# BT.net
KiCad netlist of a schematic drawn in Altium Designer
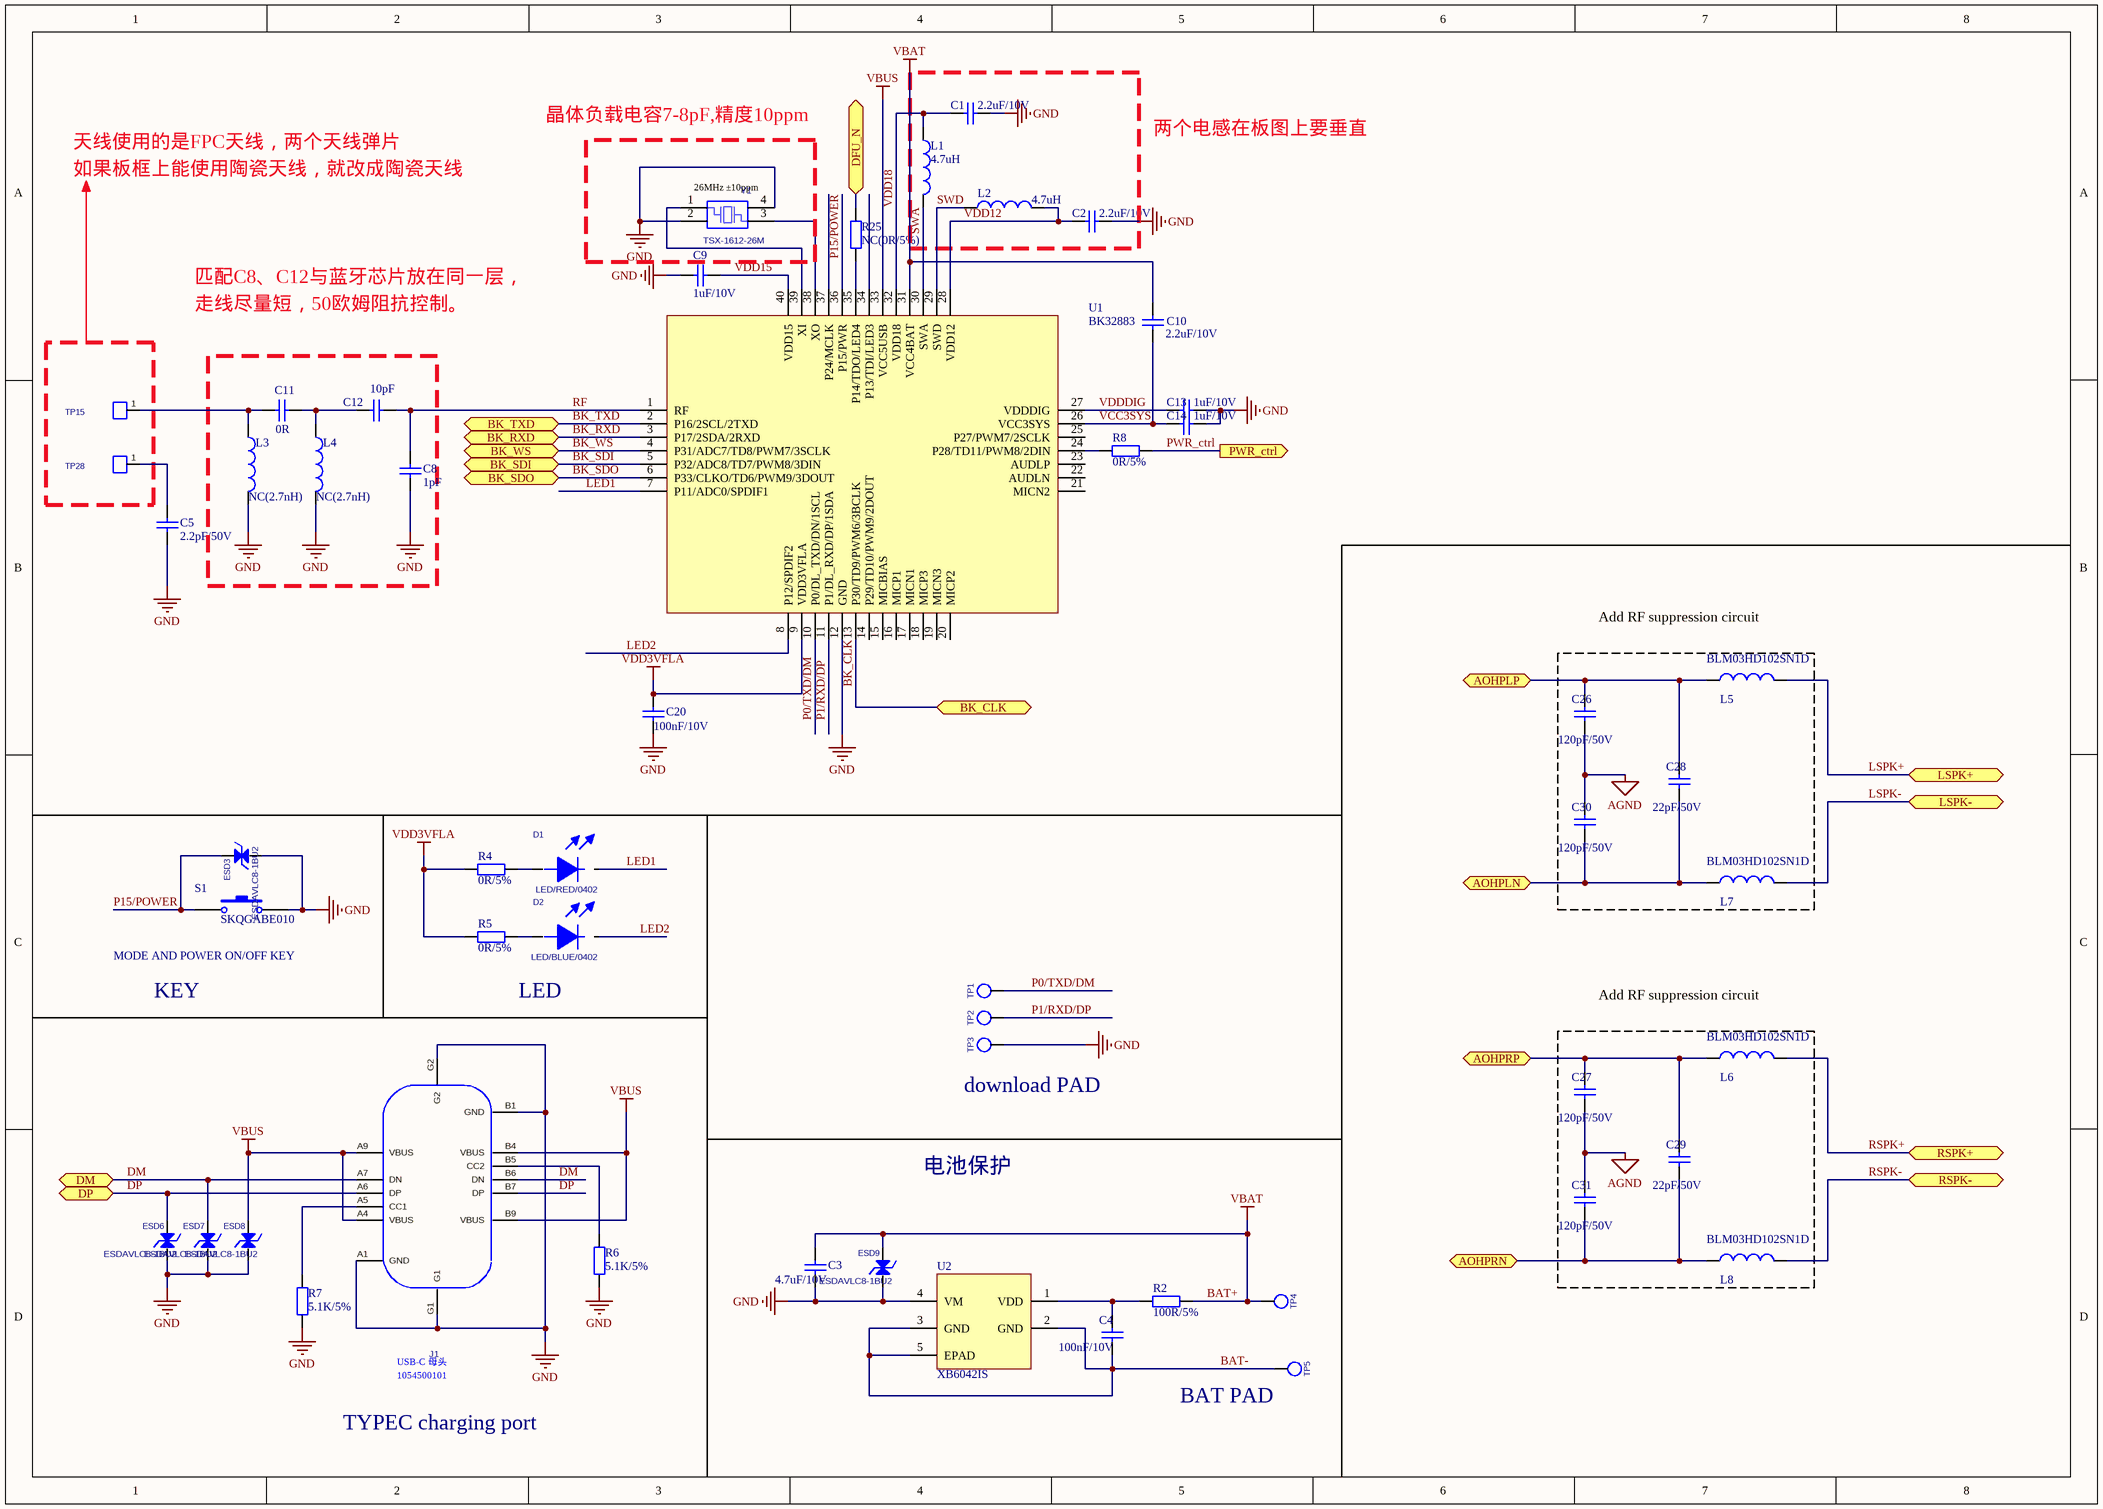
[diagram p0: BT .SchDoc]

(export (version "E")
  (design (tool "Eeschema 10.0.6"))
  (components
    (comp (ref "C1")
      (value "2.2uF/10V")
      (footprint "C0402")
      (description "Capacitor (Semiconductor SIM Model)")
      (fields (field (name "PUBLISHER") "Altium Limited"))
      (libsource (lib "Miscellaneous Devices") (part "Cap Semi"))
    )
    (comp (ref "C2")
      (value "2.2uF/10V")
      (footprint "C0402")
      (description "Capacitor (Semiconductor SIM Model)")
      (fields (field (name "PUBLISHER") "Altium Limited"))
      (libsource (lib "Miscellaneous Devices") (part "Cap Semi"))
    )
    (comp (ref "C3")
      (value "4.7uF/10V")
      (footprint "C0402")
      (description "Capacitor (Semiconductor SIM Model)")
      (fields (field (name "PUBLISHER") "Altium Limited"))
      (libsource (lib "Miscellaneous Devices") (part "Cap Semi"))
    )
    (comp (ref "C4")
      (value "100nF/10V")
      (footprint "0201")
      (description "Capacitor (Semiconductor SIM Model)")
      (fields (field (name "PUBLISHER") "Altium Limited"))
      (libsource (lib "Miscellaneous Devices") (part "Cap Semi"))
    )
    (comp (ref "C5")
      (value "2.2pF/50V")
      (footprint "0201")
      (description "Capacitor (Semiconductor SIM Model)")
      (fields (field (name "PUBLISHER") "Altium Limited"))
      (libsource (lib "Miscellaneous Devices") (part "Cap Semi"))
    )
    (comp (ref "C8")
      (value "1pF")
      (footprint "0201")
      (description "Capacitor (Semiconductor SIM Model)")
      (fields (field (name "PUBLISHER") "Altium Limited"))
      (libsource (lib "Miscellaneous Devices") (part "Cap Semi"))
    )
    (comp (ref "C9")
      (value "1uF/10V")
      (footprint "0201")
      (description "Capacitor (Semiconductor SIM Model)")
      (fields (field (name "PUBLISHER") "Altium Limited"))
      (libsource (lib "Miscellaneous Devices") (part "Cap Semi"))
    )
    (comp (ref "C10")
      (value "2.2uF/10V")
      (footprint "C0402")
      (description "Capacitor (Semiconductor SIM Model)")
      (fields (field (name "PUBLISHER") "Altium Limited"))
      (libsource (lib "Miscellaneous Devices") (part "Cap Semi"))
    )
    (comp (ref "C11")
      (value "0R")
      (footprint "0201")
      (description "Capacitor (Semiconductor SIM Model)")
      (fields (field (name "PUBLISHER") "Altium Limited"))
      (libsource (lib "Miscellaneous Devices") (part "Cap Semi"))
    )
    (comp (ref "C12")
      (value "10pF")
      (footprint "0201")
      (description "Capacitor (Semiconductor SIM Model)")
      (fields (field (name "PUBLISHER") "Altium Limited"))
      (libsource (lib "Miscellaneous Devices") (part "Cap Semi"))
    )
    (comp (ref "C13")
      (value "1uF/10V")
      (footprint "0201")
      (description "Capacitor (Semiconductor SIM Model)")
      (fields (field (name "PUBLISHER") "Altium Limited"))
      (libsource (lib "Miscellaneous Devices") (part "Cap Semi"))
    )
    (comp (ref "C14")
      (value "1uF/10V")
      (footprint "0201")
      (description "Capacitor (Semiconductor SIM Model)")
      (fields (field (name "PUBLISHER") "Altium Limited"))
      (libsource (lib "Miscellaneous Devices") (part "Cap Semi"))
    )
    (comp (ref "C20")
      (value "100nF/10V")
      (footprint "0201")
      (description "Capacitor (Semiconductor SIM Model)")
      (fields (field (name "PUBLISHER") "Altium Limited"))
      (libsource (lib "Miscellaneous Devices") (part "Cap Semi"))
    )
    (comp (ref "C26")
      (value "120pF/50V")
      (footprint "0201")
      (description "Capacitor (Semiconductor SIM Model)")
      (fields (field (name "PUBLISHER") "Altium Limited"))
      (libsource (lib "Miscellaneous Devices") (part "Cap Semi"))
    )
    (comp (ref "C27")
      (value "120pF/50V")
      (footprint "0201")
      (description "Capacitor (Semiconductor SIM Model)")
      (fields (field (name "PUBLISHER") "Altium Limited"))
      (libsource (lib "Miscellaneous Devices") (part "Cap Semi"))
    )
    (comp (ref "C28")
      (value "22pF/50V")
      (footprint "0201")
      (description "Capacitor (Semiconductor SIM Model)")
      (fields (field (name "PUBLISHER") "Altium Limited"))
      (libsource (lib "Miscellaneous Devices") (part "Cap Semi"))
    )
    (comp (ref "C29")
      (value "22pF/50V")
      (footprint "0201")
      (description "Capacitor (Semiconductor SIM Model)")
      (fields (field (name "PUBLISHER") "Altium Limited"))
      (libsource (lib "Miscellaneous Devices") (part "Cap Semi"))
    )
    (comp (ref "C30")
      (value "120pF/50V")
      (footprint "0201")
      (description "Capacitor (Semiconductor SIM Model)")
      (fields (field (name "PUBLISHER") "Altium Limited"))
      (libsource (lib "Miscellaneous Devices") (part "Cap Semi"))
    )
    (comp (ref "C31")
      (value "120pF/50V")
      (footprint "0201")
      (description "Capacitor (Semiconductor SIM Model)")
      (fields (field (name "PUBLISHER") "Altium Limited"))
      (libsource (lib "Miscellaneous Devices") (part "Cap Semi"))
    )
    (comp (ref "D1")
      (value "LED/RED/0402")
      (footprint "LED0402")
      (libsource (lib "EVB-SCH-LCD-202003152") (part "LED0603"))
    )
    (comp (ref "D2")
      (value "LED/BLUE/0402")
      (footprint "LED0402")
      (libsource (lib "EVB-SCH-LCD-202003152") (part "LED0603"))
    )
    (comp (ref "ESD3")
      (value "ESDAVLC8-1BU2")
      (footprint "0201")
      (libsource (lib "EVB-SCH-LCD-202003152") (part "ESD"))
    )
    (comp (ref "ESD6")
      (value "ESDAVLC8-1BU2")
      (footprint "0201")
      (libsource (lib "EVB-SCH-LCD-202003152") (part "ESD"))
    )
    (comp (ref "ESD7")
      (value "ESDAVLC8-1BU2")
      (footprint "0201")
      (libsource (lib "EVB-SCH-LCD-202003152") (part "ESD"))
    )
    (comp (ref "ESD8")
      (value "ESDAVLC8-1BU2")
      (footprint "0201")
      (libsource (lib "EVB-SCH-LCD-202003152") (part "ESD"))
    )
    (comp (ref "ESD9")
      (value "ESDAVLC8-1BU2")
      (footprint "0201")
      (libsource (lib "EVB-SCH-LCD-202003152") (part "ESD"))
    )
    (comp (ref "J1")
      (value "TYPEC")
      (footprint "USB-TYPEC - 12")
      (libsource (lib "EVB-SCH-LCD-202003152") (part "TYPEC"))
    )
    (comp (ref "L1")
      (value "4.7uH")
      (footprint "R0603")
      (description "Inductor")
      (fields (field (name "PUBLISHER") "Altium Limited"))
      (libsource (lib "Miscellaneous Devices") (part "Inductor"))
    )
    (comp (ref "L2")
      (value "4.7uH")
      (footprint "R0603")
      (description "Inductor")
      (fields (field (name "PUBLISHER") "Altium Limited"))
      (libsource (lib "Miscellaneous Devices") (part "Inductor"))
    )
    (comp (ref "L3")
      (value "NC(2.7nH)")
      (footprint "0201")
      (description "Inductor")
      (fields (field (name "PUBLISHER") "Altium Limited"))
      (libsource (lib "Miscellaneous Devices") (part "Inductor"))
    )
    (comp (ref "L4")
      (value "NC(2.7nH)")
      (footprint "0201")
      (description "Inductor")
      (fields (field (name "PUBLISHER") "Altium Limited"))
      (libsource (lib "Miscellaneous Devices") (part "Inductor"))
    )
    (comp (ref "L5")
      (value "BLM03HD102SN1D")
      (footprint "0201")
      (description "Inductor")
      (fields (field (name "PUBLISHER") "Altium Limited"))
      (libsource (lib "Miscellaneous Devices") (part "Inductor"))
    )
    (comp (ref "L6")
      (value "BLM03HD102SN1D")
      (footprint "0201")
      (description "Inductor")
      (fields (field (name "PUBLISHER") "Altium Limited"))
      (libsource (lib "Miscellaneous Devices") (part "Inductor"))
    )
    (comp (ref "L7")
      (value "BLM03HD102SN1D")
      (footprint "0201")
      (description "Inductor")
      (fields (field (name "PUBLISHER") "Altium Limited"))
      (libsource (lib "Miscellaneous Devices") (part "Inductor"))
    )
    (comp (ref "L8")
      (value "BLM03HD102SN1D")
      (footprint "0201")
      (description "Inductor")
      (fields (field (name "PUBLISHER") "Altium Limited"))
      (libsource (lib "Miscellaneous Devices") (part "Inductor"))
    )
    (comp (ref "R2")
      (value "100R/5%")
      (footprint "0201")
      (description "Resistor")
      (fields (field (name "PUBLISHER") "Altium Limited"))
      (libsource (lib "Miscellaneous Devices") (part "Res2"))
    )
    (comp (ref "R4")
      (value "0R/5%")
      (footprint "0201")
      (description "Resistor")
      (fields (field (name "PUBLISHER") "Altium Limited"))
      (libsource (lib "Miscellaneous Devices") (part "Res2"))
    )
    (comp (ref "R5")
      (value "0R/5%")
      (footprint "0201")
      (description "Resistor")
      (fields (field (name "PUBLISHER") "Altium Limited"))
      (libsource (lib "Miscellaneous Devices") (part "Res2"))
    )
    (comp (ref "R6")
      (value "5.1K/5%")
      (footprint "0201")
      (description "Resistor")
      (fields (field (name "PUBLISHER") "Altium Limited"))
      (libsource (lib "Miscellaneous Devices") (part "Res2"))
    )
    (comp (ref "R7")
      (value "5.1K/5%")
      (footprint "0201")
      (description "Resistor")
      (fields (field (name "PUBLISHER") "Altium Limited"))
      (libsource (lib "") (part "Res2_1"))
    )
    (comp (ref "R8")
      (value "0R/5%")
      (footprint "0201")
      (description "Resistor")
      (fields (field (name "PUBLISHER") "Altium Limited"))
      (libsource (lib "Miscellaneous Devices") (part "Res2"))
    )
    (comp (ref "R25")
      (value "NC(0R/5%)")
      (footprint "0201")
      (description "Resistor")
      (fields (field (name "PUBLISHER") "Altium Limited"))
      (libsource (lib "") (part "Res2_1"))
    )
    (comp (ref "S1")
      (value "SKQGABE010")
      (footprint "TD-302060")
      (description "Switch")
      (fields (field (name "PUBLISHER") "Altium Limited"))
      (libsource (lib "Miscellaneous Devices") (part "SW-PB"))
    )
    (comp (ref "TP1")
      (value "TP1")
      (footprint "TP1-1MM")
      (libsource (lib "EVB-SCH-LCD-202003152") (part "TP1"))
    )
    (comp (ref "TP2")
      (value "TP1")
      (footprint "TP1-1MM")
      (libsource (lib "EVB-SCH-LCD-202003152") (part "TP1"))
    )
    (comp (ref "TP3")
      (value "TP1")
      (footprint "TP1-1MM")
      (libsource (lib "EVB-SCH-LCD-202003152") (part "TP1"))
    )
    (comp (ref "TP4")
      (value "TP1")
      (footprint "TP1-1MM")
      (libsource (lib "EVB-SCH-LCD-202003152") (part "TP1"))
    )
    (comp (ref "TP5")
      (value "TP1")
      (footprint "TP1-1MM")
      (libsource (lib "EVB-SCH-LCD-202003152") (part "TP1"))
    )
    (comp (ref "TP15") (value "TP") (footprint "PAD") (libsource (lib "EVB-SCH-LCD-202003152") (part "TP")))
    (comp (ref "TP28") (value "TP") (footprint "PAD") (libsource (lib "EVB-SCH-LCD-202003152") (part "TP")))
    (comp (ref "U1")
      (value "BK32883")
      (footprint "QFN40_4X5")
      (libsource (lib "EVB-SCH-LCD-202003152") (part "BK3288_QFN40_4X5"))
    )
    (comp (ref "U2")
      (value "XB6042IS")
      (footprint "UTDFN-1X1-4")
      (libsource (lib "JGEJ_V1.0") (part "XB6042IS"))
    )
    (comp (ref "Y1")
      (value "TSX-1612-26M")
      (footprint "SF1612")
      (libsource (lib "EVB-SCH-LCD-202003152") (part "SF1612"))
    )
  )
  (nets
    (net (code "1") (name "/AOHPLN") (class "Default")
      (node (ref "C28") (pin "1") (pinfunction "1_1") (pintype "passive"))
      (node (ref "C30") (pin "1") (pinfunction "1_1") (pintype "passive"))
      (node (ref "L7") (pin "1") (pinfunction "1_1") (pintype "passive"))
    )
    (net (code "2") (name "/AOHPLP") (class "Default")
      (node (ref "C26") (pin "2") (pinfunction "2_2") (pintype "passive"))
      (node (ref "C28") (pin "2") (pinfunction "2_2") (pintype "passive"))
      (node (ref "L5") (pin "1") (pinfunction "1_1") (pintype "passive"))
    )
    (net (code "3") (name "/AOHPRN") (class "Default")
      (node (ref "C29") (pin "1") (pinfunction "1_1") (pintype "passive"))
      (node (ref "C31") (pin "1") (pinfunction "1_1") (pintype "passive"))
      (node (ref "L8") (pin "1") (pinfunction "1_1") (pintype "passive"))
    )
    (net (code "4") (name "/AOHPRP") (class "Default")
      (node (ref "C27") (pin "2") (pinfunction "2_2") (pintype "passive"))
      (node (ref "C29") (pin "2") (pinfunction "2_2") (pintype "passive"))
      (node (ref "L6") (pin "1") (pinfunction "1_1") (pintype "passive"))
    )
    (net (code "5") (name "/BAT-") (class "Default")
      (node (ref "C4") (pin "1") (pinfunction "1_1") (pintype "passive"))
      (node (ref "TP5") (pin "1") (pinfunction "1_1") (pintype "passive"))
      (node (ref "U2") (pin "2") (pinfunction "GND_2") (pintype "passive"))
      (node (ref "U2") (pin "3") (pinfunction "GND_3") (pintype "passive"))
      (node (ref "U2") (pin "5") (pinfunction "EPAD_5") (pintype "passive"))
    )
    (net (code "6") (name "/BK_CLK") (class "Default")
      (node (ref "U1") (pin "13") (pinfunction "P30/TD9/PWM6/3BCLK_13") (pintype "passive"))
    )
    (net (code "7") (name "/BK_RXD") (class "Default")
      (node (ref "U1") (pin "3") (pinfunction "P17/2SDA/2RXD_3") (pintype "passive"))
    )
    (net (code "8") (name "/BK_SDI") (class "Default")
      (node (ref "U1") (pin "5") (pinfunction "P32/ADC8/TD7/PWM8/3DIN_5") (pintype "passive"))
    )
    (net (code "9") (name "/BK_SDO") (class "Default")
      (node (ref "U1") (pin "6") (pinfunction "P33/CLKO/TD6/PWM9/3DOUT_6") (pintype "passive"))
    )
    (net (code "10") (name "/BK_TXD") (class "Default")
      (node (ref "U1") (pin "2") (pinfunction "P16/2SCL/2TXD_2") (pintype "passive"))
    )
    (net (code "11") (name "/BK_WS") (class "Default")
      (node (ref "U1") (pin "4") (pinfunction "P31/ADC7/TD8/PWM7/3SCLK_4") (pintype "passive"))
    )
    (net (code "12") (name "/DFU_N") (class "Default")
      (node (ref "R25") (pin "1") (pinfunction "1_1") (pintype "passive"))
    )
    (net (code "13") (name "/DM") (class "Default")
      (node (ref "ESD7") (pin "1") (pinfunction "1_1") (pintype "passive"))
      (node (ref "J1") (pin "A7") (pinfunction "DN_A7") (pintype "passive"))
      (node (ref "J1") (pin "B6") (pinfunction "DN_B6") (pintype "passive"))
    )
    (net (code "14") (name "/DP") (class "Default")
      (node (ref "ESD6") (pin "1") (pinfunction "1_1") (pintype "passive"))
      (node (ref "J1") (pin "A6") (pinfunction "DP_A6") (pintype "passive"))
      (node (ref "J1") (pin "B7") (pinfunction "DP_B7") (pintype "passive"))
    )
    (net (code "15") (name "/LED1") (class "Default")
      (node (ref "D1") (pin "1") (pinfunction "1_1") (pintype "passive"))
      (node (ref "U1") (pin "7") (pinfunction "P11/ADC0/SPDIF1_7") (pintype "passive"))
    )
    (net (code "16") (name "/LED2") (class "Default")
      (node (ref "D2") (pin "1") (pinfunction "1_1") (pintype "passive"))
      (node (ref "U1") (pin "8") (pinfunction "P12/SPDIF2_8") (pintype "passive"))
    )
    (net (code "17") (name "/LSPK+") (class "Default")
      (node (ref "L5") (pin "2") (pinfunction "2_2") (pintype "passive"))
    )
    (net (code "18") (name "/LSPK-") (class "Default")
      (node (ref "L7") (pin "2") (pinfunction "2_2") (pintype "passive"))
    )
    (net (code "19") (name "/P0{slash}TXD{slash}DM") (class "Default")
      (node (ref "TP1") (pin "1") (pinfunction "1_1") (pintype "passive"))
      (node (ref "U1") (pin "10") (pinfunction "P0/DL_TXD/DN/1SCL_10") (pintype "passive"))
    )
    (net (code "20") (name "/P1{slash}RXD{slash}DP") (class "Default")
      (node (ref "TP2") (pin "1") (pinfunction "1_1") (pintype "passive"))
      (node (ref "U1") (pin "11") (pinfunction "P1/DL_RXD/DP/1SDA_11") (pintype "passive"))
    )
    (net (code "21") (name "/P15{slash}POWER") (class "Default")
      (node (ref "ESD3") (pin "1") (pinfunction "1_1") (pintype "passive"))
      (node (ref "S1") (pin "2") (pinfunction "2_2") (pintype "passive"))
      (node (ref "U1") (pin "36") (pinfunction "P15/PWR_36") (pintype "passive"))
    )
    (net (code "22") (name "/PWR_ctrl") (class "Default")
      (node (ref "R8") (pin "1") (pinfunction "1_1") (pintype "passive"))
    )
    (net (code "23") (name "/RF") (class "Default")
      (node (ref "C12") (pin "1") (pinfunction "1_1") (pintype "passive"))
      (node (ref "C8") (pin "1") (pinfunction "1_1") (pintype "passive"))
      (node (ref "U1") (pin "1") (pinfunction "RF_1") (pintype "passive"))
    )
    (net (code "24") (name "/RSPK+") (class "Default")
      (node (ref "L6") (pin "2") (pinfunction "2_2") (pintype "passive"))
    )
    (net (code "25") (name "/RSPK-") (class "Default")
      (node (ref "L8") (pin "2") (pinfunction "2_2") (pintype "passive"))
    )
    (net (code "26") (name "/SWA") (class "Default")
      (node (ref "L1") (pin "2") (pinfunction "2_2") (pintype "passive"))
      (node (ref "U1") (pin "30") (pinfunction "SWA_30") (pintype "passive"))
    )
    (net (code "27") (name "/SWD") (class "Default")
      (node (ref "L2") (pin "1") (pinfunction "1_1") (pintype "passive"))
      (node (ref "U1") (pin "29") (pinfunction "SWD_29") (pintype "passive"))
    )
    (net (code "28") (name "/VCC3SYS") (class "Default")
      (node (ref "C10") (pin "1") (pinfunction "1_1") (pintype "passive"))
      (node (ref "C14") (pin "1") (pinfunction "1_1") (pintype "passive"))
      (node (ref "U1") (pin "26") (pinfunction "VCC3SYS_26") (pintype "passive"))
    )
    (net (code "29") (name "/VDD12") (class "Default")
      (node (ref "C2") (pin "1") (pinfunction "1_1") (pintype "passive"))
      (node (ref "L2") (pin "2") (pinfunction "2_2") (pintype "passive"))
      (node (ref "U1") (pin "28") (pinfunction "VDD12_28") (pintype "passive"))
    )
    (net (code "30") (name "/VDD15") (class "Default")
      (node (ref "C9") (pin "2") (pinfunction "2_2") (pintype "passive"))
      (node (ref "U1") (pin "40") (pinfunction "VDD15_40") (pintype "passive"))
    )
    (net (code "31") (name "/VDD18") (class "Default")
      (node (ref "C1") (pin "1") (pinfunction "1_1") (pintype "passive"))
      (node (ref "L1") (pin "1") (pinfunction "1_1") (pintype "passive"))
      (node (ref "U1") (pin "32") (pinfunction "VDD18_32") (pintype "passive"))
    )
    (net (code "32") (name "/VDDDIG") (class "Default")
      (node (ref "C13") (pin "1") (pinfunction "1_1") (pintype "passive"))
      (node (ref "U1") (pin "27") (pinfunction "VDDDIG_27") (pintype "passive"))
    )
    (net (code "33") (name "AGND") (class "Default")
      (node (ref "C26") (pin "1") (pinfunction "1_1") (pintype "passive"))
      (node (ref "C27") (pin "1") (pinfunction "1_1") (pintype "passive"))
      (node (ref "C30") (pin "2") (pinfunction "2_2") (pintype "passive"))
      (node (ref "C31") (pin "2") (pinfunction "2_2") (pintype "passive"))
    )
    (net (code "34") (name "GND") (class "Default")
      (node (ref "C1") (pin "2") (pinfunction "2_2") (pintype "passive"))
      (node (ref "C13") (pin "2") (pinfunction "2_2") (pintype "passive"))
      (node (ref "C14") (pin "2") (pinfunction "2_2") (pintype "passive"))
      (node (ref "C2") (pin "2") (pinfunction "2_2") (pintype "passive"))
      (node (ref "C20") (pin "2") (pinfunction "2_2") (pintype "passive"))
      (node (ref "C3") (pin "2") (pinfunction "2_2") (pintype "passive"))
      (node (ref "C5") (pin "2") (pinfunction "2_2") (pintype "passive"))
      (node (ref "C8") (pin "2") (pinfunction "2_2") (pintype "passive"))
      (node (ref "C9") (pin "1") (pinfunction "1_1") (pintype "passive"))
      (node (ref "ESD3") (pin "2") (pinfunction "2_2") (pintype "passive"))
      (node (ref "ESD6") (pin "2") (pinfunction "2_2") (pintype "passive"))
      (node (ref "ESD7") (pin "2") (pinfunction "2_2") (pintype "passive"))
      (node (ref "ESD8") (pin "2") (pinfunction "2_2") (pintype "passive"))
      (node (ref "ESD9") (pin "2") (pinfunction "2_2") (pintype "passive"))
      (node (ref "J1") (pin "A1") (pinfunction "GND_A1") (pintype "passive"))
      (node (ref "J1") (pin "B1") (pinfunction "GND_B1") (pintype "passive"))
      (node (ref "J1") (pin "G1") (pinfunction "G1_G1") (pintype "passive"))
      (node (ref "J1") (pin "G2") (pinfunction "G2_G2") (pintype "passive"))
      (node (ref "L3") (pin "2") (pinfunction "2_2") (pintype "passive"))
      (node (ref "L4") (pin "2") (pinfunction "2_2") (pintype "passive"))
      (node (ref "R6") (pin "2") (pinfunction "2_2") (pintype "passive"))
      (node (ref "R7") (pin "2") (pinfunction "2_2") (pintype "passive"))
      (node (ref "S1") (pin "1") (pinfunction "1_1") (pintype "passive"))
      (node (ref "TP3") (pin "1") (pinfunction "1_1") (pintype "passive"))
      (node (ref "U1") (pin "12") (pinfunction "GND_12") (pintype "passive"))
      (node (ref "U2") (pin "4") (pinfunction "VM_4") (pintype "passive"))
      (node (ref "Y1") (pin "2") (pinfunction "2_2") (pintype "passive"))
      (node (ref "Y1") (pin "4") (pinfunction "4_4") (pintype "passive"))
    )
    (net (code "35") (name "Net-(C5-Pad1)") (class "Default")
      (node (ref "C5") (pin "1") (pinfunction "1_1") (pintype "passive"))
      (node (ref "TP28") (pin "1") (pinfunction "1_1") (pintype "passive"))
    )
    (net (code "36") (name "Net-(C11-Pad1)") (class "Default")
      (node (ref "C11") (pin "1") (pinfunction "1_1") (pintype "passive"))
      (node (ref "C12") (pin "2") (pinfunction "2_2") (pintype "passive"))
      (node (ref "L4") (pin "1") (pinfunction "1_1") (pintype "passive"))
    )
    (net (code "37") (name "Net-(C11-Pad2)") (class "Default")
      (node (ref "C11") (pin "2") (pinfunction "2_2") (pintype "passive"))
      (node (ref "L3") (pin "1") (pinfunction "1_1") (pintype "passive"))
      (node (ref "TP15") (pin "1") (pinfunction "1_1") (pintype "passive"))
    )
    (net (code "38") (name "Net-(D1-Pad2)") (class "Default")
      (node (ref "D1") (pin "2") (pinfunction "2_2") (pintype "passive"))
      (node (ref "R4") (pin "1") (pinfunction "1_1") (pintype "passive"))
    )
    (net (code "39") (name "Net-(D2-Pad2)") (class "Default")
      (node (ref "D2") (pin "2") (pinfunction "2_2") (pintype "passive"))
      (node (ref "R5") (pin "1") (pinfunction "1_1") (pintype "passive"))
    )
    (net (code "40") (name "Net-(J1-CC1)") (class "Default")
      (node (ref "J1") (pin "A5") (pinfunction "CC1_A5") (pintype "passive"))
      (node (ref "R7") (pin "1") (pinfunction "1_1") (pintype "passive"))
    )
    (net (code "41") (name "Net-(J1-CC2)") (class "Default")
      (node (ref "J1") (pin "B5") (pinfunction "CC2_B5") (pintype "passive"))
      (node (ref "R6") (pin "1") (pinfunction "1_1") (pintype "passive"))
    )
    (net (code "42") (name "Net-(U1-P14{slash}TDO{slash}LED4)") (class "Default")
      (node (ref "R25") (pin "2") (pinfunction "2_2") (pintype "passive"))
      (node (ref "U1") (pin "35") (pinfunction "P14/TDO/LED4_35") (pintype "passive"))
    )
    (net (code "43") (name "Net-(U1-P28{slash}TD11{slash}PWM8{slash}2DIN)") (class "Default")
      (node (ref "R8") (pin "2") (pinfunction "2_2") (pintype "passive"))
      (node (ref "U1") (pin "24") (pinfunction "P28/TD11/PWM8/2DIN_24") (pintype "passive"))
    )
    (net (code "44") (name "Net-(U1-XI)") (class "Default")
      (node (ref "U1") (pin "39") (pinfunction "XI_39") (pintype "passive"))
      (node (ref "Y1") (pin "1") (pinfunction "1_1") (pintype "passive"))
    )
    (net (code "45") (name "Net-(U1-XO)") (class "Default")
      (node (ref "U1") (pin "38") (pinfunction "XO_38") (pintype "passive"))
      (node (ref "Y1") (pin "3") (pinfunction "3_3") (pintype "passive"))
    )
    (net (code "46") (name "Net-(U2-VDD)") (class "Default")
      (node (ref "C4") (pin "2") (pinfunction "2_2") (pintype "passive"))
      (node (ref "R2") (pin "2") (pinfunction "2_2") (pintype "passive"))
      (node (ref "U2") (pin "1") (pinfunction "VDD_1") (pintype "passive"))
    )
    (net (code "47") (name "VBAT") (class "Default")
      (node (ref "C10") (pin "2") (pinfunction "2_2") (pintype "passive"))
      (node (ref "C3") (pin "1") (pinfunction "1_1") (pintype "passive"))
      (node (ref "ESD9") (pin "1") (pinfunction "1_1") (pintype "passive"))
      (node (ref "R2") (pin "1") (pinfunction "1_1") (pintype "passive"))
      (node (ref "TP4") (pin "1") (pinfunction "1_1") (pintype "passive"))
      (node (ref "U1") (pin "31") (pinfunction "VCC4BAT_31") (pintype "passive"))
    )
    (net (code "48") (name "VBUS") (class "Default")
      (node (ref "ESD8") (pin "1") (pinfunction "1_1") (pintype "passive"))
      (node (ref "J1") (pin "A4") (pinfunction "VBUS_A4") (pintype "passive"))
      (node (ref "J1") (pin "A9") (pinfunction "VBUS_A9") (pintype "passive"))
      (node (ref "J1") (pin "B4") (pinfunction "VBUS_B4") (pintype "passive"))
      (node (ref "J1") (pin "B9") (pinfunction "VBUS_B9") (pintype "passive"))
      (node (ref "U1") (pin "33") (pinfunction "VCC5USB_33") (pintype "passive"))
    )
    (net (code "49") (name "VDD3VFLA") (class "Default")
      (node (ref "C20") (pin "1") (pinfunction "1_1") (pintype "passive"))
      (node (ref "R4") (pin "2") (pinfunction "2_2") (pintype "passive"))
      (node (ref "R5") (pin "2") (pinfunction "2_2") (pintype "passive"))
      (node (ref "U1") (pin "9") (pinfunction "VDD3VFLA_9") (pintype "passive"))
    )
    (net (code "50") (name "unconnected-(J1-GND-PadA12)") (class "Default")
      (node (ref "J1") (pin "A12") (pinfunction "GND_A12") (pintype "passive"))
    )
    (net (code "51") (name "unconnected-(J1-GND-PadB12)") (class "Default")
      (node (ref "J1") (pin "B12") (pinfunction "GND_B12") (pintype "passive"))
    )
    (net (code "52") (name "unconnected-(J1-PadG3)") (class "Default")
      (node (ref "J1") (pin "G3") (pinfunction "G3_G3") (pintype "passive"))
    )
    (net (code "53") (name "unconnected-(J1-PadG4)") (class "Default")
      (node (ref "J1") (pin "G4") (pinfunction "G4_G4") (pintype "passive"))
    )
    (net (code "54") (name "unconnected-(J1-PadG5)") (class "Default")
      (node (ref "J1") (pin "G5") (pinfunction "G5_G5") (pintype "passive"))
    )
    (net (code "55") (name "unconnected-(J1-PadG6)") (class "Default")
      (node (ref "J1") (pin "G6") (pinfunction "G6_G6") (pintype "passive"))
    )
    (net (code "56") (name "unconnected-(J1-RX1+-PadB11)") (class "Default")
      (node (ref "J1") (pin "B11") (pinfunction "RX1+_B11") (pintype "passive"))
    )
    (net (code "57") (name "unconnected-(J1-RX1--PadB10)") (class "Default")
      (node (ref "J1") (pin "B10") (pinfunction "RX1-_B10") (pintype "passive"))
    )
    (net (code "58") (name "unconnected-(J1-RX2+-PadA11)") (class "Default")
      (node (ref "J1") (pin "A11") (pinfunction "RX2+_A11") (pintype "passive"))
    )
    (net (code "59") (name "unconnected-(J1-RX2--PadA10)") (class "Default")
      (node (ref "J1") (pin "A10") (pinfunction "RX2-_A10") (pintype "passive"))
    )
    (net (code "60") (name "unconnected-(J1-SBU1-PadA8)") (class "Default")
      (node (ref "J1") (pin "A8") (pinfunction "SBU1_A8") (pintype "passive"))
    )
    (net (code "61") (name "unconnected-(J1-SBU2-PadB8)") (class "Default")
      (node (ref "J1") (pin "B8") (pinfunction "SBU2_B8") (pintype "passive"))
    )
    (net (code "62") (name "unconnected-(J1-TX1+-PadA2)") (class "Default")
      (node (ref "J1") (pin "A2") (pinfunction "TX1+_A2") (pintype "passive"))
    )
    (net (code "63") (name "unconnected-(J1-TX1--PadA3)") (class "Default")
      (node (ref "J1") (pin "A3") (pinfunction "TX1-_A3") (pintype "passive"))
    )
    (net (code "64") (name "unconnected-(J1-TX2+-PadB2)") (class "Default")
      (node (ref "J1") (pin "B2") (pinfunction "TX2+_B2") (pintype "passive"))
    )
    (net (code "65") (name "unconnected-(J1-TX2--PadB3)") (class "Default")
      (node (ref "J1") (pin "B3") (pinfunction "TX2-_B3") (pintype "passive"))
    )
    (net (code "66") (name "unconnected-(U1-AUDLN-Pad22)") (class "Default")
      (node (ref "U1") (pin "22") (pinfunction "AUDLN_22") (pintype "passive"))
    )
    (net (code "67") (name "unconnected-(U1-AUDLP-Pad23)") (class "Default")
      (node (ref "U1") (pin "23") (pinfunction "AUDLP_23") (pintype "passive"))
    )
    (net (code "68") (name "unconnected-(U1-MICBIAS-Pad15)") (class "Default")
      (node (ref "U1") (pin "15") (pinfunction "MICBIAS_15") (pintype "passive"))
    )
    (net (code "69") (name "unconnected-(U1-MICN1-Pad17)") (class "Default")
      (node (ref "U1") (pin "17") (pinfunction "MICN1_17") (pintype "passive"))
    )
    (net (code "70") (name "unconnected-(U1-MICN2-Pad21)") (class "Default")
      (node (ref "U1") (pin "21") (pinfunction "MICN2_21") (pintype "passive"))
    )
    (net (code "71") (name "unconnected-(U1-MICN3-Pad19)") (class "Default")
      (node (ref "U1") (pin "19") (pinfunction "MICN3_19") (pintype "passive"))
    )
    (net (code "72") (name "unconnected-(U1-MICP1-Pad16)") (class "Default")
      (node (ref "U1") (pin "16") (pinfunction "MICP1_16") (pintype "passive"))
    )
    (net (code "73") (name "unconnected-(U1-MICP2-Pad20)") (class "Default")
      (node (ref "U1") (pin "20") (pinfunction "MICP2_20") (pintype "passive"))
    )
    (net (code "74") (name "unconnected-(U1-MICP3-Pad18)") (class "Default")
      (node (ref "U1") (pin "18") (pinfunction "MICP3_18") (pintype "passive"))
    )
    (net (code "75") (name "unconnected-(U1-P13{slash}TDI{slash}LED3-Pad34)") (class "Default")
      (node (ref "U1") (pin "34") (pinfunction "P13/TDI/LED3_34") (pintype "passive"))
    )
    (net (code "76") (name "unconnected-(U1-P24{slash}MCLK-Pad37)") (class "Default")
      (node (ref "U1") (pin "37") (pinfunction "P24/MCLK_37") (pintype "passive"))
    )
    (net (code "77") (name "unconnected-(U1-P27{slash}PWM7{slash}2SCLK-Pad25)") (class "Default")
      (node (ref "U1") (pin "25") (pinfunction "P27/PWM7/2SCLK_25") (pintype "passive"))
    )
    (net (code "78") (name "unconnected-(U1-P29{slash}TD10{slash}PWM9{slash}2DOUT-Pad14)") (class "Default")
      (node (ref "U1") (pin "14") (pinfunction "P29/TD10/PWM9/2DOUT_14") (pintype "passive"))
    )
  )
)
